# IRIS1-DLB.net
KiCad netlist of a schematic drawn in Altium Designer
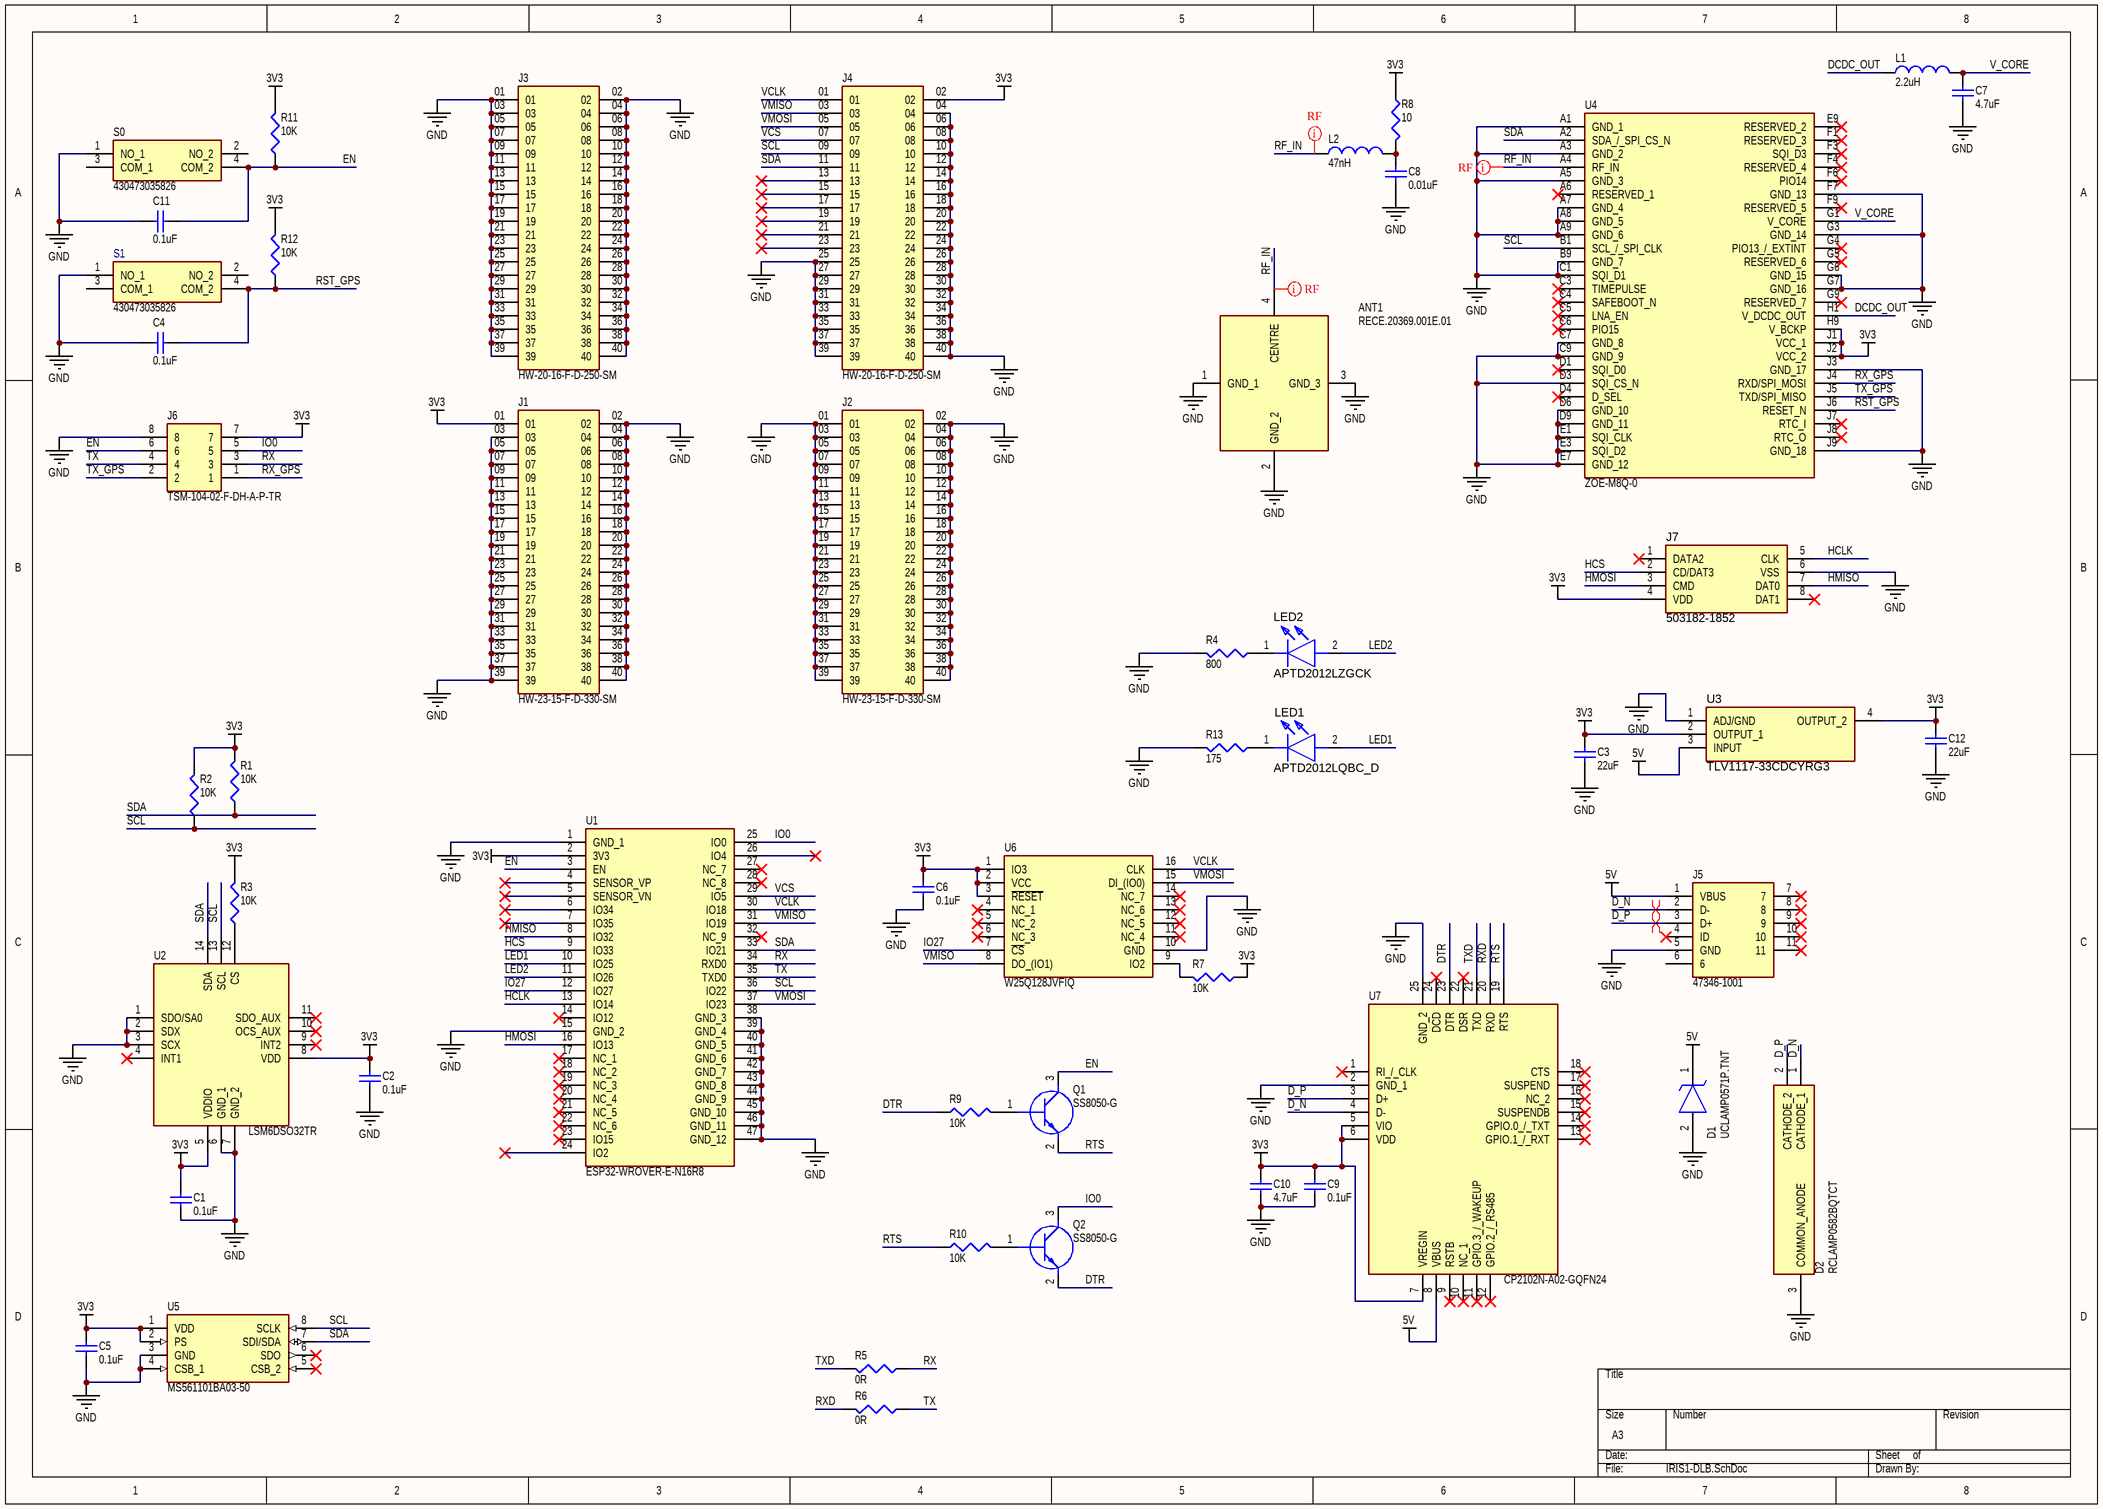
[diagram p0: IRIS1-DLB.SchDoc]

(export (version "E")
  (design (tool "Eeschema 10.0.6"))
  (components
    (comp (ref "ANT1")
      (value "RECE.20369.001E.01")
      (footprint "SamacSys:RECE20369001E01")
      (description "Antenna")
      (fields (field (name "MOUSER PART NUMBER") "960-RECE.20369001E01"))
      (libsource (lib "*") (part "RECE.20369.001E.01"))
    )
    (comp (ref "C1")
      (value "0.1uF")
      (footprint "1608[0603]")
      (description "Capacitor")
      (fields (field (name "PUBLISHER") "Altium Limited"))
      (libsource (lib "Miscellaneous Devices") (part "Cap"))
    )
    (comp (ref "C2")
      (value "0.1uF")
      (footprint "1608[0603]")
      (description "Capacitor")
      (fields (field (name "PUBLISHER") "Altium Limited"))
      (libsource (lib "Miscellaneous Devices") (part "Cap"))
    )
    (comp (ref "C3")
      (value "22uF")
      (footprint "1608[0603]")
      (description "Capacitor")
      (fields (field (name "PUBLISHER") "Altium Limited"))
      (libsource (lib "Miscellaneous Devices") (part "Cap"))
    )
    (comp (ref "C4")
      (value "0.1uF")
      (footprint "1608[0603]")
      (description "Capacitor")
      (fields (field (name "PUBLISHER") "Altium Limited"))
      (libsource (lib "Miscellaneous Devices") (part "Cap"))
    )
    (comp (ref "C5")
      (value "0.1uF")
      (footprint "1608[0603]")
      (description "Capacitor")
      (fields (field (name "PUBLISHER") "Altium Limited"))
      (libsource (lib "Miscellaneous Devices") (part "Cap"))
    )
    (comp (ref "C6")
      (value "0.1uF")
      (footprint "1608[0603]")
      (description "Capacitor")
      (fields (field (name "PUBLISHER") "Altium Limited"))
      (libsource (lib "Miscellaneous Devices") (part "Cap"))
    )
    (comp (ref "C7")
      (value "4.7uF")
      (footprint "1608[0603]")
      (description "Capacitor")
      (fields (field (name "PUBLISHER") "Altium Limited"))
      (libsource (lib "Miscellaneous Devices") (part "Cap"))
    )
    (comp (ref "C8")
      (value "0.01uF")
      (footprint "1608[0603]")
      (description "Capacitor")
      (fields (field (name "PUBLISHER") "Altium Limited"))
      (libsource (lib "Miscellaneous Devices") (part "Cap"))
    )
    (comp (ref "C9")
      (value "0.1uF")
      (footprint "1608[0603]")
      (description "Capacitor")
      (fields (field (name "PUBLISHER") "Altium Limited"))
      (libsource (lib "Miscellaneous Devices") (part "Cap"))
    )
    (comp (ref "C10")
      (value "4.7uF")
      (footprint "1608[0603]")
      (description "Capacitor")
      (fields (field (name "PUBLISHER") "Altium Limited"))
      (libsource (lib "Miscellaneous Devices") (part "Cap"))
    )
    (comp (ref "C11")
      (value "0.1uF")
      (footprint "1608[0603]")
      (description "Capacitor")
      (fields (field (name "PUBLISHER") "Altium Limited"))
      (libsource (lib "Miscellaneous Devices") (part "Cap"))
    )
    (comp (ref "C12")
      (value "22uF")
      (footprint "1608[0603]")
      (description "Capacitor")
      (fields (field (name "PUBLISHER") "Altium Limited"))
      (libsource (lib "Miscellaneous Devices") (part "Cap"))
    )
    (comp (ref "D1")
      (value "UCLAMP0571P.TNT")
      (footprint "SamacSys:DIOC1610X55N")
      (description "TVS Diode (Uni-directional)")
      (fields (field (name "MOUSER PART NUMBER") "947-UCLAMP0571P.TNT"))
      (libsource (lib "*") (part "UCLAMP0571P.TNT"))
    )
    (comp (ref "D2")
      (value "RCLAMP0582BQTCT")
      (footprint "SamacSys:SOT50P160X90-3N")
      (description "TVS Diode (Uni-directional)")
      (fields (field (name "MOUSER PART NUMBER") "947-RCLAMP0582BQTCT"))
      (libsource (lib "*") (part "RCLAMP0582BQTCT"))
    )
    (comp (ref "J1")
      (value "HW-23-15-F-D-330-SM")
      (footprint "SAMTEC_HW-20-16-F-D-250-SM")
      (fields (field (name "MF") "Samtec") (field (name "MP") "HW-20-08-G-D-350-100"))
      (libsource (lib "HW-20-XX-XX-D-XXX-XXX") (part "HW-20-XX-XX-D-XXX-XXX"))
    )
    (comp (ref "J2")
      (value "HW-23-15-F-D-330-SM")
      (footprint "SAMTEC_HW-20-16-F-D-250-SM")
      (fields (field (name "MF") "Samtec") (field (name "MP") "HW-20-08-G-D-350-100"))
      (libsource (lib "HW-20-XX-XX-D-XXX-XXX") (part "HW-20-XX-XX-D-XXX-XXX"))
    )
    (comp (ref "J3")
      (value "HW-20-16-F-D-250-SM")
      (footprint "SAMTEC_HW-20-16-F-D-250-SM")
      (libsource (lib "HW-20-16-F-D-250-SM") (part "HW-20-16-F-D-250-SM"))
    )
    (comp (ref "J4")
      (value "HW-20-16-F-D-250-SM")
      (footprint "SAMTEC_HW-20-16-F-D-250-SM")
      (libsource (lib "HW-20-16-F-D-250-SM") (part "HW-20-16-F-D-250-SM"))
    )
    (comp (ref "J5")
      (value "47346-1001")
      (footprint "SamacSys:473461001")
      (description "Connector")
      (fields (field (name "MOUSER PART NUMBER") "538-47346-1001"))
      (libsource (lib "*") (part "47346-1001"))
    )
    (comp (ref "J6")
      (value "TSM-104-02-F-DH-A-P-TR")
      (footprint "SamacSys:TSM-104-ZZ-YYY-DH-A-P-TR")
      (description "Connector")
      (libsource (lib "*") (part "TSM-104-02-F-DH-A-P-TR"))
    )
    (comp (ref "J7")
      (value "503182-1852")
      (footprint "SamacSys:5031821852")
      (description "Connector")
      (fields (field (name "MOUSER PART NUMBER") "538-503182-1852"))
      (libsource (lib "*") (part "503182-1852"))
    )
    (comp (ref "L1")
      (value "2.2uH")
      (footprint "0402-A")
      (description "Inductor")
      (fields (field (name "PUBLISHER") "Altium Limited"))
      (libsource (lib "Miscellaneous Devices") (part "Inductor"))
    )
    (comp (ref "L2")
      (value "47nH")
      (footprint "0402-A")
      (description "Inductor")
      (fields (field (name "PUBLISHER") "Altium Limited"))
      (libsource (lib "Miscellaneous Devices") (part "Inductor"))
    )
    (comp (ref "LED1")
      (value "APTD2012LQBC_D")
      (footprint "SamacSys:LEDC2012X120N")
      (description "LED")
      (fields
        (field (name "MANUFACTURER_PART_NUMBER") "APTD2012LQBC/D")
        (field (name "MOUSER PART NUMBER") "604-APTD2012LQBCD")
      )
      (libsource (lib "*") (part "APTD2012LQBC_D"))
    )
    (comp (ref "LED2")
      (value "APTD2012LZGCK")
      (footprint "SamacSys:LEDC2012X105N")
      (description "LED")
      (fields (field (name "MOUSER PART NUMBER") "604-APTD2012LZGCK"))
      (libsource (lib "*") (part "APTD2012LZGCK"))
    )
    (comp (ref "Q1")
      (value "SS8050-G")
      (footprint "SamacSys:SOT95P240X115-3N")
      (description "Transistor BJT NPN")
      (fields (field (name "MOUSER PART NUMBER") "750-SS8050-G"))
      (libsource (lib "*") (part "SS8050-G"))
    )
    (comp (ref "Q2")
      (value "SS8050-G")
      (footprint "SamacSys:SOT95P240X115-3N")
      (description "Transistor BJT NPN")
      (fields (field (name "MOUSER PART NUMBER") "750-SS8050-G"))
      (libsource (lib "*") (part "SS8050-G"))
    )
    (comp (ref "R1")
      (value "10K")
      (footprint "J1-0603")
      (description "Resistor")
      (fields (field (name "PUBLISHER") "Altium Limited"))
      (libsource (lib "Miscellaneous Devices") (part "Res3"))
    )
    (comp (ref "R2")
      (value "10K")
      (footprint "J1-0603")
      (description "Resistor")
      (fields (field (name "PUBLISHER") "Altium Limited"))
      (libsource (lib "Miscellaneous Devices") (part "Res3"))
    )
    (comp (ref "R3")
      (value "10K")
      (footprint "J1-0603")
      (description "Resistor")
      (fields (field (name "PUBLISHER") "Altium Limited"))
      (libsource (lib "Miscellaneous Devices") (part "Res3"))
    )
    (comp (ref "R4")
      (value "800")
      (footprint "J1-0603")
      (description "Resistor")
      (fields (field (name "PUBLISHER") "Altium Limited"))
      (libsource (lib "Miscellaneous Devices") (part "Res3"))
    )
    (comp (ref "R5")
      (value "0R")
      (footprint "J1-0603")
      (description "Resistor")
      (fields (field (name "PUBLISHER") "Altium Limited"))
      (libsource (lib "Miscellaneous Devices") (part "Res3"))
    )
    (comp (ref "R6")
      (value "0R")
      (footprint "J1-0603")
      (description "Resistor")
      (fields (field (name "PUBLISHER") "Altium Limited"))
      (libsource (lib "Miscellaneous Devices") (part "Res3"))
    )
    (comp (ref "R7")
      (value "10K")
      (footprint "J1-0603")
      (description "Resistor")
      (fields (field (name "PUBLISHER") "Altium Limited"))
      (libsource (lib "Miscellaneous Devices") (part "Res3"))
    )
    (comp (ref "R8")
      (value "10")
      (footprint "J1-0603")
      (description "Resistor")
      (fields (field (name "PUBLISHER") "Altium Limited"))
      (libsource (lib "Miscellaneous Devices") (part "Res3"))
    )
    (comp (ref "R9")
      (value "10K")
      (footprint "J1-0603")
      (description "Resistor")
      (fields (field (name "PUBLISHER") "Altium Limited"))
      (libsource (lib "Miscellaneous Devices") (part "Res3"))
    )
    (comp (ref "R10")
      (value "10K")
      (footprint "J1-0603")
      (description "Resistor")
      (fields (field (name "PUBLISHER") "Altium Limited"))
      (libsource (lib "Miscellaneous Devices") (part "Res3"))
    )
    (comp (ref "R11")
      (value "10K")
      (footprint "J1-0603")
      (description "Resistor")
      (fields (field (name "PUBLISHER") "Altium Limited"))
      (libsource (lib "Miscellaneous Devices") (part "Res3"))
    )
    (comp (ref "R12")
      (value "10K")
      (footprint "J1-0603")
      (description "Resistor")
      (fields (field (name "PUBLISHER") "Altium Limited"))
      (libsource (lib "Miscellaneous Devices") (part "Res3"))
    )
    (comp (ref "R13")
      (value "175")
      (footprint "J1-0603")
      (description "Resistor")
      (fields (field (name "PUBLISHER") "Altium Limited"))
      (libsource (lib "Miscellaneous Devices") (part "Res3"))
    )
    (comp (ref "S0")
      (value "430473035826")
      (footprint "SamacSys:430473035826")
      (description "Switch")
      (fields (field (name "MOUSER PART NUMBER") "710-430473035826"))
      (libsource (lib "*") (part "430473035826"))
    )
    (comp (ref "S1")
      (value "430473035826")
      (footprint "SamacSys:430473035826")
      (description "Switch")
      (fields (field (name "MOUSER PART NUMBER") "710-430473035826"))
      (libsource (lib "*") (part "430473035826"))
    )
    (comp (ref "U1")
      (value "ESP32-WROVER-E-N16R8")
      (footprint "SamacSys:ESP32WROVEREN16R8")
      (description "Integrated Circuit")
      (fields (field (name "MOUSER PART NUMBER") "356-ESP32WRVE22864PC"))
      (libsource (lib "*") (part "ESP32-WROVER-E-N16R8"))
    )
    (comp (ref "U2")
      (value "LSM6DSO32TR")
      (footprint "SamacSys:LGA-14(2.5X3X0.86)")
      (description "Accelerometer")
      (fields
        (field (name "MANUFACTURER_PART_NUMBER") "LSM6DSOTR")
        (field (name "MOUSER PART NUMBER") "511-LSM6DSOTR")
      )
      (libsource (lib "*") (part "LSM6DSOTR"))
    )
    (comp (ref "U3")
      (value "TLV1117-33CDCYRG3")
      (footprint "SamacSys:SOT230P700X180-4N")
      (description "Integrated Circuit")
      (fields (field (name "MOUSER PART NUMBER") "595-TLV111733CDCYRG3"))
      (libsource (lib "*") (part "TLV1117-33CDCYRG3"))
    )
    (comp (ref "U4")
      (value "ZOE-M8Q-0")
      (footprint "SamacSys:ZOEM8Q0")
      (description "Integrated Circuit")
      (fields (field (name "MOUSER PART NUMBER") "377-ZOE-M8Q-0"))
      (libsource (lib "*") (part "ZOE-M8Q-0"))
    )
    (comp (ref "U5")
      (value "MS561101BA03-50")
      (footprint "SamacSys:MS561101BA03-50")
      (description "Integrated Circuit")
      (fields (field (name "MOUSER PART NUMBER") "824-MS561101BA03-50"))
      (libsource (lib "*") (part "MS561101BA03-50"))
    )
    (comp (ref "U6")
      (value "W25Q128JVFIQ")
      (footprint "SamacSys:SOIC127P1032X264-16N")
      (description "Integrated Circuit")
      (fields (field (name "MOUSER PART NUMBER") "454-W25Q128JVFIQ"))
      (libsource (lib "*") (part "W25Q128JVFIQ"))
    )
    (comp (ref "U7")
      (value "CP2102N-A02-GQFN24")
      (footprint "SamacSys:QFN50P400X400X80-25N-D")
      (description "Integrated Circuit")
      (fields (field (name "MOUSER PART NUMBER") "634-CP2102NA02GQFN24"))
      (libsource (lib "*") (part "CP2102N-A02-GQFN24"))
    )
  )
  (nets
    (net (code "1") (name "/DCDC_OUT") (class "Default")
      (node (ref "L1") (pin "1") (pinfunction "1_1") (pintype "passive"))
      (node (ref "U4") (pin "H1") (pinfunction "V_DCDC_OUT_H1") (pintype "passive"))
    )
    (net (code "2") (name "/DTR") (class "Default")
      (node (ref "Q2") (pin "2") (pinfunction "E_2") (pintype "passive"))
      (node (ref "R9") (pin "1") (pinfunction "1_1") (pintype "passive"))
      (node (ref "U7") (pin "23") (pinfunction "DTR_23") (pintype "passive"))
    )
    (net (code "3") (name "/D_N") (class "Default")
      (node (ref "D2") (pin "1") (pinfunction "CATHODE_1_1") (pintype "passive"))
      (node (ref "J5") (pin "2") (pinfunction "D-_2") (pintype "passive"))
      (node (ref "U7") (pin "4") (pinfunction "D-_4") (pintype "passive"))
    )
    (net (code "4") (name "/D_P") (class "Default")
      (node (ref "D2") (pin "2") (pinfunction "CATHODE_2_2") (pintype "passive"))
      (node (ref "J5") (pin "3") (pinfunction "D+_3") (pintype "passive"))
      (node (ref "U7") (pin "3") (pinfunction "D+_3") (pintype "passive"))
    )
    (net (code "5") (name "/EN") (class "Default")
      (node (ref "C11") (pin "2") (pinfunction "2_2") (pintype "passive"))
      (node (ref "J6") (pin "6") (pinfunction "6_6") (pintype "passive"))
      (node (ref "Q1") (pin "3") (pinfunction "C_3") (pintype "passive"))
      (node (ref "R11") (pin "1") (pinfunction "1_1") (pintype "passive"))
      (node (ref "S0") (pin "4") (pinfunction "COM_2_4") (pintype "passive"))
      (node (ref "U1") (pin "3") (pinfunction "EN_3") (pintype "passive"))
    )
    (net (code "6") (name "/HCLK") (class "Default")
      (node (ref "J7") (pin "5") (pinfunction "CLK_5") (pintype "passive"))
      (node (ref "U1") (pin "13") (pinfunction "IO14_13") (pintype "passive"))
    )
    (net (code "7") (name "/HCS") (class "Default")
      (node (ref "J7") (pin "2") (pinfunction "CD/DAT3_2") (pintype "passive"))
      (node (ref "U1") (pin "9") (pinfunction "IO33_9") (pintype "passive"))
    )
    (net (code "8") (name "/HMISO") (class "Default")
      (node (ref "J7") (pin "7") (pinfunction "DAT0_7") (pintype "passive"))
      (node (ref "U1") (pin "8") (pinfunction "IO32_8") (pintype "passive"))
    )
    (net (code "9") (name "/HMOSI") (class "Default")
      (node (ref "J7") (pin "3") (pinfunction "CMD_3") (pintype "passive"))
      (node (ref "U1") (pin "16") (pinfunction "IO13_16") (pintype "passive"))
    )
    (net (code "10") (name "/IO0") (class "Default")
      (node (ref "J6") (pin "5") (pinfunction "5_5") (pintype "passive"))
      (node (ref "Q2") (pin "3") (pinfunction "C_3") (pintype "passive"))
      (node (ref "U1") (pin "25") (pinfunction "IO0_25") (pintype "passive"))
    )
    (net (code "11") (name "/IO27") (class "Default")
      (node (ref "U1") (pin "12") (pinfunction "IO27_12") (pintype "passive"))
      (node (ref "U6") (pin "7") (pinfunction "~{CS}_7") (pintype "passive"))
    )
    (net (code "12") (name "/LED1") (class "Default")
      (node (ref "LED1") (pin "2") (pinfunction "A_2") (pintype "passive"))
      (node (ref "U1") (pin "10") (pinfunction "IO25_10") (pintype "passive"))
    )
    (net (code "13") (name "/LED2") (class "Default")
      (node (ref "LED2") (pin "2") (pinfunction "A_2") (pintype "passive"))
      (node (ref "U1") (pin "11") (pinfunction "IO26_11") (pintype "passive"))
    )
    (net (code "14") (name "/RF_IN") (class "Default")
      (node (ref "ANT1") (pin "4") (pinfunction "CENTRE_4") (pintype "passive"))
      (node (ref "L2") (pin "1") (pinfunction "1_1") (pintype "passive"))
      (node (ref "U4") (pin "A4") (pinfunction "RF_IN_A4") (pintype "passive"))
    )
    (net (code "15") (name "/RST_GPS") (class "Default")
      (node (ref "C4") (pin "2") (pinfunction "2_2") (pintype "passive"))
      (node (ref "R12") (pin "1") (pinfunction "1_1") (pintype "passive"))
      (node (ref "S1") (pin "4") (pinfunction "COM_2_4") (pintype "passive"))
      (node (ref "U4") (pin "J6") (pinfunction "RESET_N_J6") (pintype "passive"))
    )
    (net (code "16") (name "/RTS") (class "Default")
      (node (ref "Q1") (pin "2") (pinfunction "E_2") (pintype "passive"))
      (node (ref "R10") (pin "1") (pinfunction "1_1") (pintype "passive"))
      (node (ref "U7") (pin "19") (pinfunction "RTS_19") (pintype "passive"))
    )
    (net (code "17") (name "/RX") (class "Default")
      (node (ref "J6") (pin "3") (pinfunction "3_3") (pintype "passive"))
      (node (ref "R5") (pin "1") (pinfunction "1_1") (pintype "passive"))
      (node (ref "U1") (pin "34") (pinfunction "RXD0_34") (pintype "passive"))
    )
    (net (code "18") (name "/RXD") (class "Default")
      (node (ref "R6") (pin "2") (pinfunction "2_2") (pintype "passive"))
      (node (ref "U7") (pin "20") (pinfunction "RXD_20") (pintype "passive"))
    )
    (net (code "19") (name "/RX_GPS") (class "Default")
      (node (ref "J6") (pin "1") (pinfunction "1_1") (pintype "passive"))
      (node (ref "U4") (pin "J4") (pinfunction "RXD/SPI_MOSI_J4") (pintype "passive"))
    )
    (net (code "20") (name "/SCL") (class "Default")
      (node (ref "J4") (pin "09") (pinfunction "09_09") (pintype "passive"))
      (node (ref "R2") (pin "1") (pinfunction "1_1") (pintype "passive"))
      (node (ref "U1") (pin "36") (pinfunction "IO22_36") (pintype "passive"))
      (node (ref "U2") (pin "13") (pinfunction "SCL_13") (pintype "passive"))
      (node (ref "U4") (pin "B1") (pinfunction "SCL_/_SPI_CLK_B1") (pintype "passive"))
      (node (ref "U5") (pin "8") (pinfunction "SCLK_8") (pintype "input"))
    )
    (net (code "21") (name "/SDA") (class "Default")
      (node (ref "J4") (pin "11") (pinfunction "11_11") (pintype "passive"))
      (node (ref "R1") (pin "1") (pinfunction "1_1") (pintype "passive"))
      (node (ref "U1") (pin "33") (pinfunction "IO21_33") (pintype "passive"))
      (node (ref "U2") (pin "14") (pinfunction "SDA_14") (pintype "passive"))
      (node (ref "U4") (pin "A2") (pinfunction "SDA_/_SPI_CS_N_A2") (pintype "passive"))
      (node (ref "U5") (pin "7") (pinfunction "SDI/SDA_7") (pintype "bidirectional"))
    )
    (net (code "22") (name "/TX") (class "Default")
      (node (ref "J6") (pin "4") (pinfunction "4_4") (pintype "passive"))
      (node (ref "R6") (pin "1") (pinfunction "1_1") (pintype "passive"))
      (node (ref "U1") (pin "35") (pinfunction "TXD0_35") (pintype "passive"))
    )
    (net (code "23") (name "/TXD") (class "Default")
      (node (ref "R5") (pin "2") (pinfunction "2_2") (pintype "passive"))
      (node (ref "U7") (pin "21") (pinfunction "TXD_21") (pintype "passive"))
    )
    (net (code "24") (name "/TX_GPS") (class "Default")
      (node (ref "J6") (pin "2") (pinfunction "2_2") (pintype "passive"))
      (node (ref "U4") (pin "J5") (pinfunction "TXD/SPI_MISO_J5") (pintype "passive"))
    )
    (net (code "25") (name "/VCLK") (class "Default")
      (node (ref "J4") (pin "01") (pinfunction "01_01") (pintype "passive"))
      (node (ref "U1") (pin "30") (pinfunction "IO18_30") (pintype "passive"))
      (node (ref "U6") (pin "16") (pinfunction "CLK_16") (pintype "passive"))
    )
    (net (code "26") (name "/VCS") (class "Default")
      (node (ref "J4") (pin "07") (pinfunction "07_07") (pintype "passive"))
      (node (ref "U1") (pin "29") (pinfunction "IO5_29") (pintype "passive"))
    )
    (net (code "27") (name "/VMISO") (class "Default")
      (node (ref "J4") (pin "03") (pinfunction "03_03") (pintype "passive"))
      (node (ref "U1") (pin "31") (pinfunction "IO19_31") (pintype "passive"))
      (node (ref "U6") (pin "8") (pinfunction "DO_(IO1)_8") (pintype "passive"))
    )
    (net (code "28") (name "/VMOSI") (class "Default")
      (node (ref "J4") (pin "05") (pinfunction "05_05") (pintype "passive"))
      (node (ref "U1") (pin "37") (pinfunction "IO23_37") (pintype "passive"))
      (node (ref "U6") (pin "15") (pinfunction "DI_(IO0)_15") (pintype "passive"))
    )
    (net (code "29") (name "/V_CORE") (class "Default")
      (node (ref "C7") (pin "2") (pinfunction "2_2") (pintype "passive"))
      (node (ref "L1") (pin "2") (pinfunction "2_2") (pintype "passive"))
      (node (ref "U4") (pin "G1") (pinfunction "V_CORE_G1") (pintype "passive"))
    )
    (net (code "30") (name "3V3") (class "Default")
      (node (ref "C1") (pin "2") (pinfunction "2_2") (pintype "passive"))
      (node (ref "C10") (pin "2") (pinfunction "2_2") (pintype "passive"))
      (node (ref "C12") (pin "2") (pinfunction "2_2") (pintype "passive"))
      (node (ref "C2") (pin "2") (pinfunction "2_2") (pintype "passive"))
      (node (ref "C3") (pin "2") (pinfunction "2_2") (pintype "passive"))
      (node (ref "C5") (pin "2") (pinfunction "2_2") (pintype "passive"))
      (node (ref "C6") (pin "2") (pinfunction "2_2") (pintype "passive"))
      (node (ref "C9") (pin "2") (pinfunction "2_2") (pintype "passive"))
      (node (ref "J1") (pin "01") (pinfunction "01_01") (pintype "passive"))
      (node (ref "J4") (pin "02") (pinfunction "02_02") (pintype "passive"))
      (node (ref "J6") (pin "7") (pinfunction "7_7") (pintype "passive"))
      (node (ref "J7") (pin "4") (pinfunction "VDD_4") (pintype "passive"))
      (node (ref "R1") (pin "2") (pinfunction "2_2") (pintype "passive"))
      (node (ref "R11") (pin "2") (pinfunction "2_2") (pintype "passive"))
      (node (ref "R12") (pin "2") (pinfunction "2_2") (pintype "passive"))
      (node (ref "R2") (pin "2") (pinfunction "2_2") (pintype "passive"))
      (node (ref "R3") (pin "2") (pinfunction "2_2") (pintype "passive"))
      (node (ref "R7") (pin "1") (pinfunction "1_1") (pintype "passive"))
      (node (ref "R8") (pin "1") (pinfunction "1_1") (pintype "passive"))
      (node (ref "U1") (pin "2") (pinfunction "3V3_2") (pintype "passive"))
      (node (ref "U2") (pin "5") (pinfunction "VDDIO_5") (pintype "passive"))
      (node (ref "U2") (pin "8") (pinfunction "VDD_8") (pintype "passive"))
      (node (ref "U3") (pin "2") (pinfunction "OUTPUT_1_2") (pintype "passive"))
      (node (ref "U3") (pin "4") (pinfunction "OUTPUT_2_4") (pintype "passive"))
      (node (ref "U4") (pin "H9") (pinfunction "V_BCKP_H9") (pintype "passive"))
      (node (ref "U4") (pin "J1") (pinfunction "VCC_1_J1") (pintype "passive"))
      (node (ref "U4") (pin "J2") (pinfunction "VCC_2_J2") (pintype "passive"))
      (node (ref "U5") (pin "1") (pinfunction "VDD_1") (pintype "power_in"))
      (node (ref "U5") (pin "2") (pinfunction "PS_2") (pintype "input"))
      (node (ref "U6") (pin "1") (pinfunction "IO3_1") (pintype "passive"))
      (node (ref "U6") (pin "2") (pinfunction "VCC_2") (pintype "passive"))
      (node (ref "U6") (pin "3") (pinfunction "~{RESET}_3") (pintype "passive"))
      (node (ref "U7") (pin "5") (pinfunction "VIO_5") (pintype "passive"))
      (node (ref "U7") (pin "6") (pinfunction "VDD_6") (pintype "passive"))
      (node (ref "U7") (pin "7") (pinfunction "VREGIN_7") (pintype "passive"))
    )
    (net (code "31") (name "5V") (class "Default")
      (node (ref "D1") (pin "1") (pinfunction "K_1") (pintype "passive"))
      (node (ref "J5") (pin "1") (pinfunction "VBUS_1") (pintype "passive"))
      (node (ref "U3") (pin "3") (pinfunction "INPUT_3") (pintype "passive"))
      (node (ref "U7") (pin "8") (pinfunction "VBUS_8") (pintype "passive"))
    )
    (net (code "32") (name "GND") (class "Default")
      (node (ref "ANT1") (pin "1") (pinfunction "GND_1_1") (pintype "passive"))
      (node (ref "ANT1") (pin "2") (pinfunction "GND_2_2") (pintype "passive"))
      (node (ref "ANT1") (pin "3") (pinfunction "GND_3_3") (pintype "passive"))
      (node (ref "C1") (pin "1") (pinfunction "1_1") (pintype "passive"))
      (node (ref "C10") (pin "1") (pinfunction "1_1") (pintype "passive"))
      (node (ref "C11") (pin "1") (pinfunction "1_1") (pintype "passive"))
      (node (ref "C12") (pin "1") (pinfunction "1_1") (pintype "passive"))
      (node (ref "C2") (pin "1") (pinfunction "1_1") (pintype "passive"))
      (node (ref "C3") (pin "1") (pinfunction "1_1") (pintype "passive"))
      (node (ref "C4") (pin "1") (pinfunction "1_1") (pintype "passive"))
      (node (ref "C5") (pin "1") (pinfunction "1_1") (pintype "passive"))
      (node (ref "C6") (pin "1") (pinfunction "1_1") (pintype "passive"))
      (node (ref "C7") (pin "1") (pinfunction "1_1") (pintype "passive"))
      (node (ref "C8") (pin "1") (pinfunction "1_1") (pintype "passive"))
      (node (ref "C9") (pin "1") (pinfunction "1_1") (pintype "passive"))
      (node (ref "D1") (pin "2") (pinfunction "A_2") (pintype "passive"))
      (node (ref "D2") (pin "3") (pinfunction "COMMON_ANODE_3") (pintype "passive"))
      (node (ref "J1") (pin "02") (pinfunction "02_02") (pintype "passive"))
      (node (ref "J1") (pin "03") (pinfunction "03_03") (pintype "passive"))
      (node (ref "J1") (pin "04") (pinfunction "04_04") (pintype "passive"))
      (node (ref "J1") (pin "05") (pinfunction "05_05") (pintype "passive"))
      (node (ref "J1") (pin "06") (pinfunction "06_06") (pintype "passive"))
      (node (ref "J1") (pin "07") (pinfunction "07_07") (pintype "passive"))
      (node (ref "J1") (pin "08") (pinfunction "08_08") (pintype "passive"))
      (node (ref "J1") (pin "09") (pinfunction "09_09") (pintype "passive"))
      (node (ref "J1") (pin "10") (pinfunction "10_10") (pintype "passive"))
      (node (ref "J1") (pin "11") (pinfunction "11_11") (pintype "passive"))
      (node (ref "J1") (pin "12") (pinfunction "12_12") (pintype "passive"))
      (node (ref "J1") (pin "13") (pinfunction "13_13") (pintype "passive"))
      (node (ref "J1") (pin "14") (pinfunction "14_14") (pintype "passive"))
      (node (ref "J1") (pin "15") (pinfunction "15_15") (pintype "passive"))
      (node (ref "J1") (pin "16") (pinfunction "16_16") (pintype "passive"))
      (node (ref "J1") (pin "17") (pinfunction "17_17") (pintype "passive"))
      (node (ref "J1") (pin "18") (pinfunction "18_18") (pintype "passive"))
      (node (ref "J1") (pin "19") (pinfunction "19_19") (pintype "passive"))
      (node (ref "J1") (pin "20") (pinfunction "20_20") (pintype "passive"))
      (node (ref "J1") (pin "21") (pinfunction "21_21") (pintype "passive"))
      (node (ref "J1") (pin "22") (pinfunction "22_22") (pintype "passive"))
      (node (ref "J1") (pin "23") (pinfunction "23_23") (pintype "passive"))
      (node (ref "J1") (pin "24") (pinfunction "24_24") (pintype "passive"))
      (node (ref "J1") (pin "25") (pinfunction "25_25") (pintype "passive"))
      (node (ref "J1") (pin "26") (pinfunction "26_26") (pintype "passive"))
      (node (ref "J1") (pin "27") (pinfunction "27_27") (pintype "passive"))
      (node (ref "J1") (pin "28") (pinfunction "28_28") (pintype "passive"))
      (node (ref "J1") (pin "29") (pinfunction "29_29") (pintype "passive"))
      (node (ref "J1") (pin "30") (pinfunction "30_30") (pintype "passive"))
      (node (ref "J1") (pin "31") (pinfunction "31_31") (pintype "passive"))
      (node (ref "J1") (pin "32") (pinfunction "32_32") (pintype "passive"))
      (node (ref "J1") (pin "33") (pinfunction "33_33") (pintype "passive"))
      (node (ref "J1") (pin "34") (pinfunction "34_34") (pintype "passive"))
      (node (ref "J1") (pin "35") (pinfunction "35_35") (pintype "passive"))
      (node (ref "J1") (pin "36") (pinfunction "36_36") (pintype "passive"))
      (node (ref "J1") (pin "37") (pinfunction "37_37") (pintype "passive"))
      (node (ref "J1") (pin "38") (pinfunction "38_38") (pintype "passive"))
      (node (ref "J1") (pin "39") (pinfunction "39_39") (pintype "passive"))
      (node (ref "J1") (pin "40") (pinfunction "40_40") (pintype "passive"))
      (node (ref "J2") (pin "01") (pinfunction "01_01") (pintype "passive"))
      (node (ref "J2") (pin "02") (pinfunction "02_02") (pintype "passive"))
      (node (ref "J2") (pin "03") (pinfunction "03_03") (pintype "passive"))
      (node (ref "J2") (pin "04") (pinfunction "04_04") (pintype "passive"))
      (node (ref "J2") (pin "05") (pinfunction "05_05") (pintype "passive"))
      (node (ref "J2") (pin "06") (pinfunction "06_06") (pintype "passive"))
      (node (ref "J2") (pin "07") (pinfunction "07_07") (pintype "passive"))
      (node (ref "J2") (pin "08") (pinfunction "08_08") (pintype "passive"))
      (node (ref "J2") (pin "09") (pinfunction "09_09") (pintype "passive"))
      (node (ref "J2") (pin "10") (pinfunction "10_10") (pintype "passive"))
      (node (ref "J2") (pin "11") (pinfunction "11_11") (pintype "passive"))
      (node (ref "J2") (pin "12") (pinfunction "12_12") (pintype "passive"))
      (node (ref "J2") (pin "13") (pinfunction "13_13") (pintype "passive"))
      (node (ref "J2") (pin "14") (pinfunction "14_14") (pintype "passive"))
      (node (ref "J2") (pin "15") (pinfunction "15_15") (pintype "passive"))
      (node (ref "J2") (pin "16") (pinfunction "16_16") (pintype "passive"))
      (node (ref "J2") (pin "17") (pinfunction "17_17") (pintype "passive"))
      (node (ref "J2") (pin "18") (pinfunction "18_18") (pintype "passive"))
      (node (ref "J2") (pin "19") (pinfunction "19_19") (pintype "passive"))
      (node (ref "J2") (pin "20") (pinfunction "20_20") (pintype "passive"))
      (node (ref "J2") (pin "21") (pinfunction "21_21") (pintype "passive"))
      (node (ref "J2") (pin "22") (pinfunction "22_22") (pintype "passive"))
      (node (ref "J2") (pin "23") (pinfunction "23_23") (pintype "passive"))
      (node (ref "J2") (pin "24") (pinfunction "24_24") (pintype "passive"))
      (node (ref "J2") (pin "25") (pinfunction "25_25") (pintype "passive"))
      (node (ref "J2") (pin "26") (pinfunction "26_26") (pintype "passive"))
      (node (ref "J2") (pin "27") (pinfunction "27_27") (pintype "passive"))
      (node (ref "J2") (pin "28") (pinfunction "28_28") (pintype "passive"))
      (node (ref "J2") (pin "29") (pinfunction "29_29") (pintype "passive"))
      (node (ref "J2") (pin "30") (pinfunction "30_30") (pintype "passive"))
      (node (ref "J2") (pin "31") (pinfunction "31_31") (pintype "passive"))
      (node (ref "J2") (pin "32") (pinfunction "32_32") (pintype "passive"))
      (node (ref "J2") (pin "33") (pinfunction "33_33") (pintype "passive"))
      (node (ref "J2") (pin "34") (pinfunction "34_34") (pintype "passive"))
      (node (ref "J2") (pin "35") (pinfunction "35_35") (pintype "passive"))
      (node (ref "J2") (pin "36") (pinfunction "36_36") (pintype "passive"))
      (node (ref "J2") (pin "37") (pinfunction "37_37") (pintype "passive"))
      (node (ref "J2") (pin "38") (pinfunction "38_38") (pintype "passive"))
      (node (ref "J2") (pin "39") (pinfunction "39_39") (pintype "passive"))
      (node (ref "J2") (pin "40") (pinfunction "40_40") (pintype "passive"))
      (node (ref "J3") (pin "01") (pinfunction "01_01") (pintype "passive"))
      (node (ref "J3") (pin "02") (pinfunction "02_02") (pintype "passive"))
      (node (ref "J3") (pin "03") (pinfunction "03_03") (pintype "passive"))
      (node (ref "J3") (pin "04") (pinfunction "04_04") (pintype "passive"))
      (node (ref "J3") (pin "05") (pinfunction "05_05") (pintype "passive"))
      (node (ref "J3") (pin "06") (pinfunction "06_06") (pintype "passive"))
      (node (ref "J3") (pin "07") (pinfunction "07_07") (pintype "passive"))
      (node (ref "J3") (pin "08") (pinfunction "08_08") (pintype "passive"))
      (node (ref "J3") (pin "09") (pinfunction "09_09") (pintype "passive"))
      (node (ref "J3") (pin "10") (pinfunction "10_10") (pintype "passive"))
      (node (ref "J3") (pin "11") (pinfunction "11_11") (pintype "passive"))
      (node (ref "J3") (pin "12") (pinfunction "12_12") (pintype "passive"))
      (node (ref "J3") (pin "13") (pinfunction "13_13") (pintype "passive"))
      (node (ref "J3") (pin "14") (pinfunction "14_14") (pintype "passive"))
      (node (ref "J3") (pin "15") (pinfunction "15_15") (pintype "passive"))
      (node (ref "J3") (pin "16") (pinfunction "16_16") (pintype "passive"))
      (node (ref "J3") (pin "17") (pinfunction "17_17") (pintype "passive"))
      (node (ref "J3") (pin "18") (pinfunction "18_18") (pintype "passive"))
      (node (ref "J3") (pin "19") (pinfunction "19_19") (pintype "passive"))
      (node (ref "J3") (pin "20") (pinfunction "20_20") (pintype "passive"))
      (node (ref "J3") (pin "21") (pinfunction "21_21") (pintype "passive"))
      (node (ref "J3") (pin "22") (pinfunction "22_22") (pintype "passive"))
      (node (ref "J3") (pin "23") (pinfunction "23_23") (pintype "passive"))
      (node (ref "J3") (pin "24") (pinfunction "24_24") (pintype "passive"))
      (node (ref "J3") (pin "25") (pinfunction "25_25") (pintype "passive"))
      (node (ref "J3") (pin "26") (pinfunction "26_26") (pintype "passive"))
      (node (ref "J3") (pin "27") (pinfunction "27_27") (pintype "passive"))
      (node (ref "J3") (pin "28") (pinfunction "28_28") (pintype "passive"))
      (node (ref "J3") (pin "29") (pinfunction "29_29") (pintype "passive"))
      (node (ref "J3") (pin "30") (pinfunction "30_30") (pintype "passive"))
      (node (ref "J3") (pin "31") (pinfunction "31_31") (pintype "passive"))
      (node (ref "J3") (pin "32") (pinfunction "32_32") (pintype "passive"))
      (node (ref "J3") (pin "33") (pinfunction "33_33") (pintype "passive"))
      (node (ref "J3") (pin "34") (pinfunction "34_34") (pintype "passive"))
      (node (ref "J3") (pin "35") (pinfunction "35_35") (pintype "passive"))
      (node (ref "J3") (pin "36") (pinfunction "36_36") (pintype "passive"))
      (node (ref "J3") (pin "37") (pinfunction "37_37") (pintype "passive"))
      (node (ref "J3") (pin "38") (pinfunction "38_38") (pintype "passive"))
      (node (ref "J3") (pin "39") (pinfunction "39_39") (pintype "passive"))
      (node (ref "J3") (pin "40") (pinfunction "40_40") (pintype "passive"))
      (node (ref "J4") (pin "04") (pinfunction "04_04") (pintype "passive"))
      (node (ref "J4") (pin "06") (pinfunction "06_06") (pintype "passive"))
      (node (ref "J4") (pin "08") (pinfunction "08_08") (pintype "passive"))
      (node (ref "J4") (pin "10") (pinfunction "10_10") (pintype "passive"))
      (node (ref "J4") (pin "12") (pinfunction "12_12") (pintype "passive"))
      (node (ref "J4") (pin "14") (pinfunction "14_14") (pintype "passive"))
      (node (ref "J4") (pin "16") (pinfunction "16_16") (pintype "passive"))
      (node (ref "J4") (pin "18") (pinfunction "18_18") (pintype "passive"))
      (node (ref "J4") (pin "20") (pinfunction "20_20") (pintype "passive"))
      (node (ref "J4") (pin "22") (pinfunction "22_22") (pintype "passive"))
      (node (ref "J4") (pin "24") (pinfunction "24_24") (pintype "passive"))
      (node (ref "J4") (pin "25") (pinfunction "25_25") (pintype "passive"))
      (node (ref "J4") (pin "26") (pinfunction "26_26") (pintype "passive"))
      (node (ref "J4") (pin "27") (pinfunction "27_27") (pintype "passive"))
      (node (ref "J4") (pin "28") (pinfunction "28_28") (pintype "passive"))
      (node (ref "J4") (pin "29") (pinfunction "29_29") (pintype "passive"))
      (node (ref "J4") (pin "30") (pinfunction "30_30") (pintype "passive"))
      (node (ref "J4") (pin "31") (pinfunction "31_31") (pintype "passive"))
      (node (ref "J4") (pin "32") (pinfunction "32_32") (pintype "passive"))
      (node (ref "J4") (pin "33") (pinfunction "33_33") (pintype "passive"))
      (node (ref "J4") (pin "34") (pinfunction "34_34") (pintype "passive"))
      (node (ref "J4") (pin "35") (pinfunction "35_35") (pintype "passive"))
      (node (ref "J4") (pin "36") (pinfunction "36_36") (pintype "passive"))
      (node (ref "J4") (pin "37") (pinfunction "37_37") (pintype "passive"))
      (node (ref "J4") (pin "38") (pinfunction "38_38") (pintype "passive"))
      (node (ref "J4") (pin "39") (pinfunction "39_39") (pintype "passive"))
      (node (ref "J4") (pin "40") (pinfunction "40_40") (pintype "passive"))
      (node (ref "J5") (pin "5") (pinfunction "GND_5") (pintype "passive"))
      (node (ref "J6") (pin "8") (pinfunction "8_8") (pintype "passive"))
      (node (ref "J7") (pin "6") (pinfunction "VSS_6") (pintype "passive"))
      (node (ref "R13") (pin "2") (pinfunction "2_2") (pintype "passive"))
      (node (ref "R4") (pin "2") (pinfunction "2_2") (pintype "passive"))
      (node (ref "S0") (pin "1") (pinfunction "NO_1_1") (pintype "passive"))
      (node (ref "S1") (pin "1") (pinfunction "NO_1_1") (pintype "passive"))
      (node (ref "U1") (pin "1") (pinfunction "GND_1_1") (pintype "passive"))
      (node (ref "U1") (pin "15") (pinfunction "GND_2_15") (pintype "passive"))
      (node (ref "U1") (pin "38") (pinfunction "GND_3_38") (pintype "passive"))
      (node (ref "U1") (pin "39") (pinfunction "GND_4_39") (pintype "passive"))
      (node (ref "U1") (pin "40") (pinfunction "GND_5_40") (pintype "passive"))
      (node (ref "U1") (pin "41") (pinfunction "GND_6_41") (pintype "passive"))
      (node (ref "U1") (pin "42") (pinfunction "GND_7_42") (pintype "passive"))
      (node (ref "U1") (pin "43") (pinfunction "GND_8_43") (pintype "passive"))
      (node (ref "U1") (pin "44") (pinfunction "GND_9_44") (pintype "passive"))
      (node (ref "U1") (pin "45") (pinfunction "GND_10_45") (pintype "passive"))
      (node (ref "U1") (pin "46") (pinfunction "GND_11_46") (pintype "passive"))
      (node (ref "U1") (pin "47") (pinfunction "GND_12_47") (pintype "passive"))
      (node (ref "U2") (pin "1") (pinfunction "SDO/SA0_1") (pintype "passive"))
      (node (ref "U2") (pin "2") (pinfunction "SDX_2") (pintype "passive"))
      (node (ref "U2") (pin "3") (pinfunction "SCX_3") (pintype "passive"))
      (node (ref "U2") (pin "6") (pinfunction "GND_1_6") (pintype "passive"))
      (node (ref "U2") (pin "7") (pinfunction "GND_2_7") (pintype "passive"))
      (node (ref "U3") (pin "1") (pinfunction "ADJ/GND_1") (pintype "passive"))
      (node (ref "U4") (pin "A1") (pinfunction "GND_1_A1") (pintype "passive"))
      (node (ref "U4") (pin "A3") (pinfunction "GND_2_A3") (pintype "passive"))
      (node (ref "U4") (pin "A5") (pinfunction "GND_3_A5") (pintype "passive"))
      (node (ref "U4") (pin "A7") (pinfunction "GND_4_A7") (pintype "passive"))
      (node (ref "U4") (pin "A8") (pinfunction "GND_5_A8") (pintype "passive"))
      (node (ref "U4") (pin "A9") (pinfunction "GND_6_A9") (pintype "passive"))
      (node (ref "U4") (pin "B9") (pinfunction "GND_7_B9") (pintype "passive"))
      (node (ref "U4") (pin "C1") (pinfunction "SQI_D1_C1") (pintype "passive"))
      (node (ref "U4") (pin "C7") (pinfunction "GND_8_C7") (pintype "passive"))
      (node (ref "U4") (pin "C9") (pinfunction "GND_9_C9") (pintype "passive"))
      (node (ref "U4") (pin "D3") (pinfunction "SQI_CS_N_D3") (pintype "passive"))
      (node (ref "U4") (pin "D6") (pinfunction "GND_10_D6") (pintype "passive"))
      (node (ref "U4") (pin "D9") (pinfunction "GND_11_D9") (pintype "passive"))
      (node (ref "U4") (pin "E1") (pinfunction "SQI_CLK_E1") (pintype "passive"))
      (node (ref "U4") (pin "E3") (pinfunction "SQI_D2_E3") (pintype "passive"))
      (node (ref "U4") (pin "E7") (pinfunction "GND_12_E7") (pintype "passive"))
      (node (ref "U4") (pin "F7") (pinfunction "GND_13_F7") (pintype "passive"))
      (node (ref "U4") (pin "G3") (pinfunction "GND_14_G3") (pintype "passive"))
      (node (ref "U4") (pin "G6") (pinfunction "GND_15_G6") (pintype "passive"))
      (node (ref "U4") (pin "G7") (pinfunction "GND_16_G7") (pintype "passive"))
      (node (ref "U4") (pin "J3") (pinfunction "GND_17_J3") (pintype "passive"))
      (node (ref "U4") (pin "J9") (pinfunction "GND_18_J9") (pintype "passive"))
      (node (ref "U5") (pin "3") (pinfunction "GND_3") (pintype "power_in"))
      (node (ref "U5") (pin "4") (pinfunction "CSB_1_4") (pintype "input"))
      (node (ref "U6") (pin "10") (pinfunction "GND_10") (pintype "passive"))
      (node (ref "U7") (pin "2") (pinfunction "GND_1_2") (pintype "passive"))
      (node (ref "U7") (pin "25") (pinfunction "GND_2_25") (pintype "passive"))
    )
    (net (code "33") (name "Net-(C8-Pad2)") (class "Default")
      (node (ref "C8") (pin "2") (pinfunction "2_2") (pintype "passive"))
      (node (ref "L2") (pin "2") (pinfunction "2_2") (pintype "passive"))
      (node (ref "R8") (pin "2") (pinfunction "2_2") (pintype "passive"))
    )
    (net (code "34") (name "Net-(LED1-K)") (class "Default")
      (node (ref "LED1") (pin "1") (pinfunction "K_1") (pintype "passive"))
      (node (ref "R13") (pin "1") (pinfunction "1_1") (pintype "passive"))
    )
    (net (code "35") (name "Net-(LED2-K)") (class "Default")
      (node (ref "LED2") (pin "1") (pinfunction "K_1") (pintype "passive"))
      (node (ref "R4") (pin "1") (pinfunction "1_1") (pintype "passive"))
    )
    (net (code "36") (name "Net-(Q1-B)") (class "Default")
      (node (ref "Q1") (pin "1") (pinfunction "B_1") (pintype "passive"))
      (node (ref "R9") (pin "2") (pinfunction "2_2") (pintype "passive"))
    )
    (net (code "37") (name "Net-(Q2-B)") (class "Default")
      (node (ref "Q2") (pin "1") (pinfunction "B_1") (pintype "passive"))
      (node (ref "R10") (pin "2") (pinfunction "2_2") (pintype "passive"))
    )
    (net (code "38") (name "Net-(U2-CS)") (class "Default")
      (node (ref "R3") (pin "1") (pinfunction "1_1") (pintype "passive"))
      (node (ref "U2") (pin "12") (pinfunction "CS_12") (pintype "passive"))
    )
    (net (code "39") (name "Net-(U6-IO2)") (class "Default")
      (node (ref "R7") (pin "2") (pinfunction "2_2") (pintype "passive"))
      (node (ref "U6") (pin "9") (pinfunction "IO2_9") (pintype "passive"))
    )
    (net (code "40") (name "unconnected-(J4-Pad13)") (class "Default")
      (node (ref "J4") (pin "13") (pinfunction "13_13") (pintype "passive+no_connect"))
    )
    (net (code "41") (name "unconnected-(J4-Pad15)") (class "Default")
      (node (ref "J4") (pin "15") (pinfunction "15_15") (pintype "passive+no_connect"))
    )
    (net (code "42") (name "unconnected-(J4-Pad17)") (class "Default")
      (node (ref "J4") (pin "17") (pinfunction "17_17") (pintype "passive+no_connect"))
    )
    (net (code "43") (name "unconnected-(J4-Pad19)") (class "Default")
      (node (ref "J4") (pin "19") (pinfunction "19_19") (pintype "passive+no_connect"))
    )
    (net (code "44") (name "unconnected-(J4-Pad21)") (class "Default")
      (node (ref "J4") (pin "21") (pinfunction "21_21") (pintype "passive+no_connect"))
    )
    (net (code "45") (name "unconnected-(J4-Pad23)") (class "Default")
      (node (ref "J4") (pin "23") (pinfunction "23_23") (pintype "passive+no_connect"))
    )
    (net (code "46") (name "unconnected-(J5-ID-Pad4)") (class "Default")
      (node (ref "J5") (pin "4") (pinfunction "ID_4") (pintype "passive+no_connect"))
    )
    (net (code "47") (name "unconnected-(J5-Pad6)") (class "Default")
      (node (ref "J5") (pin "6") (pinfunction "6_6") (pintype "passive"))
    )
    (net (code "48") (name "unconnected-(J5-Pad7)") (class "Default")
      (node (ref "J5") (pin "7") (pinfunction "7_7") (pintype "passive+no_connect"))
    )
    (net (code "49") (name "unconnected-(J5-Pad8)") (class "Default")
      (node (ref "J5") (pin "8") (pinfunction "8_8") (pintype "passive+no_connect"))
    )
    (net (code "50") (name "unconnected-(J5-Pad9)") (class "Default")
      (node (ref "J5") (pin "9") (pinfunction "9_9") (pintype "passive+no_connect"))
    )
    (net (code "51") (name "unconnected-(J5-Pad10)") (class "Default")
      (node (ref "J5") (pin "10") (pinfunction "10_10") (pintype "passive+no_connect"))
    )
    (net (code "52") (name "unconnected-(J5-Pad11)") (class "Default")
      (node (ref "J5") (pin "11") (pinfunction "11_11") (pintype "passive+no_connect"))
    )
    (net (code "53") (name "unconnected-(J7-DAT1-Pad8)") (class "Default")
      (node (ref "J7") (pin "8") (pinfunction "DAT1_8") (pintype "passive+no_connect"))
    )
    (net (code "54") (name "unconnected-(J7-DATA2-Pad1)") (class "Default")
      (node (ref "J7") (pin "1") (pinfunction "DATA2_1") (pintype "passive+no_connect"))
    )
    (net (code "55") (name "unconnected-(S0-COM_1-Pad3)") (class "Default")
      (node (ref "S0") (pin "3") (pinfunction "COM_1_3") (pintype "passive"))
    )
    (net (code "56") (name "unconnected-(S0-NO_2-Pad2)") (class "Default")
      (node (ref "S0") (pin "2") (pinfunction "NO_2_2") (pintype "passive"))
    )
    (net (code "57") (name "unconnected-(S1-COM_1-Pad3)") (class "Default")
      (node (ref "S1") (pin "3") (pinfunction "COM_1_3") (pintype "passive"))
    )
    (net (code "58") (name "unconnected-(S1-NO_2-Pad2)") (class "Default")
      (node (ref "S1") (pin "2") (pinfunction "NO_2_2") (pintype "passive"))
    )
    (net (code "59") (name "unconnected-(U1-IO2-Pad24)") (class "Default")
      (node (ref "U1") (pin "24") (pinfunction "IO2_24") (pintype "passive+no_connect"))
    )
    (net (code "60") (name "unconnected-(U1-IO4-Pad26)") (class "Default")
      (node (ref "U1") (pin "26") (pinfunction "IO4_26") (pintype "passive+no_connect"))
    )
    (net (code "61") (name "unconnected-(U1-IO12-Pad14)") (class "Default")
      (node (ref "U1") (pin "14") (pinfunction "IO12_14") (pintype "passive+no_connect"))
    )
    (net (code "62") (name "unconnected-(U1-IO15-Pad23)") (class "Default")
      (node (ref "U1") (pin "23") (pinfunction "IO15_23") (pintype "passive+no_connect"))
    )
    (net (code "63") (name "unconnected-(U1-IO34-Pad6)") (class "Default")
      (node (ref "U1") (pin "6") (pinfunction "IO34_6") (pintype "passive+no_connect"))
    )
    (net (code "64") (name "unconnected-(U1-IO35-Pad7)") (class "Default")
      (node (ref "U1") (pin "7") (pinfunction "IO35_7") (pintype "passive+no_connect"))
    )
    (net (code "65") (name "unconnected-(U1-NC_1-Pad17)") (class "Default")
      (node (ref "U1") (pin "17") (pinfunction "NC_1_17") (pintype "passive+no_connect"))
    )
    (net (code "66") (name "unconnected-(U1-NC_2-Pad18)") (class "Default")
      (node (ref "U1") (pin "18") (pinfunction "NC_2_18") (pintype "passive+no_connect"))
    )
    (net (code "67") (name "unconnected-(U1-NC_3-Pad19)") (class "Default")
      (node (ref "U1") (pin "19") (pinfunction "NC_3_19") (pintype "passive+no_connect"))
    )
    (net (code "68") (name "unconnected-(U1-NC_4-Pad20)") (class "Default")
      (node (ref "U1") (pin "20") (pinfunction "NC_4_20") (pintype "passive+no_connect"))
    )
    (net (code "69") (name "unconnected-(U1-NC_5-Pad21)") (class "Default")
      (node (ref "U1") (pin "21") (pinfunction "NC_5_21") (pintype "passive+no_connect"))
    )
    (net (code "70") (name "unconnected-(U1-NC_6-Pad22)") (class "Default")
      (node (ref "U1") (pin "22") (pinfunction "NC_6_22") (pintype "passive+no_connect"))
    )
    (net (code "71") (name "unconnected-(U1-NC_7-Pad27)") (class "Default")
      (node (ref "U1") (pin "27") (pinfunction "NC_7_27") (pintype "passive+no_connect"))
    )
    (net (code "72") (name "unconnected-(U1-NC_8-Pad28)") (class "Default")
      (node (ref "U1") (pin "28") (pinfunction "NC_8_28") (pintype "passive+no_connect"))
    )
    (net (code "73") (name "unconnected-(U1-NC_9-Pad32)") (class "Default")
      (node (ref "U1") (pin "32") (pinfunction "NC_9_32") (pintype "passive+no_connect"))
    )
    (net (code "74") (name "unconnected-(U1-SENSOR_VN-Pad5)") (class "Default")
      (node (ref "U1") (pin "5") (pinfunction "SENSOR_VN_5") (pintype "passive+no_connect"))
    )
    (net (code "75") (name "unconnected-(U1-SENSOR_VP-Pad4)") (class "Default")
      (node (ref "U1") (pin "4") (pinfunction "SENSOR_VP_4") (pintype "passive+no_connect"))
    )
    (net (code "76") (name "unconnected-(U2-INT1-Pad4)") (class "Default")
      (node (ref "U2") (pin "4") (pinfunction "INT1_4") (pintype "passive+no_connect"))
    )
    (net (code "77") (name "unconnected-(U2-INT2-Pad9)") (class "Default")
      (node (ref "U2") (pin "9") (pinfunction "INT2_9") (pintype "passive+no_connect"))
    )
    (net (code "78") (name "unconnected-(U2-OCS_AUX-Pad10)") (class "Default")
      (node (ref "U2") (pin "10") (pinfunction "OCS_AUX_10") (pintype "passive+no_connect"))
    )
    (net (code "79") (name "unconnected-(U2-SDO_AUX-Pad11)") (class "Default")
      (node (ref "U2") (pin "11") (pinfunction "SDO_AUX_11") (pintype "passive+no_connect"))
    )
    (net (code "80") (name "unconnected-(U4-D_SEL-PadD4)") (class "Default")
      (node (ref "U4") (pin "D4") (pinfunction "D_SEL_D4") (pintype "passive+no_connect"))
    )
    (net (code "81") (name "unconnected-(U4-LNA_EN-PadC5)") (class "Default")
      (node (ref "U4") (pin "C5") (pinfunction "LNA_EN_C5") (pintype "passive+no_connect"))
    )
    (net (code "82") (name "unconnected-(U4-PIO13_{slash}_EXTINT-PadG4)") (class "Default")
      (node (ref "U4") (pin "G4") (pinfunction "PIO13_/_EXTINT_G4") (pintype "passive+no_connect"))
    )
    (net (code "83") (name "unconnected-(U4-PIO14-PadF6)") (class "Default")
      (node (ref "U4") (pin "F6") (pinfunction "PIO14_F6") (pintype "passive+no_connect"))
    )
    (net (code "84") (name "unconnected-(U4-PIO15-PadC6)") (class "Default")
      (node (ref "U4") (pin "C6") (pinfunction "PIO15_C6") (pintype "passive+no_connect"))
    )
    (net (code "85") (name "unconnected-(U4-RESERVED_1-PadA6)") (class "Default")
      (node (ref "U4") (pin "A6") (pinfunction "RESERVED_1_A6") (pintype "passive+no_connect"))
    )
    (net (code "86") (name "unconnected-(U4-RESERVED_2-PadE9)") (class "Default")
      (node (ref "U4") (pin "E9") (pinfunction "RESERVED_2_E9") (pintype "passive+no_connect"))
    )
    (net (code "87") (name "unconnected-(U4-RESERVED_3-PadF1)") (class "Default")
      (node (ref "U4") (pin "F1") (pinfunction "RESERVED_3_F1") (pintype "passive+no_connect"))
    )
    (net (code "88") (name "unconnected-(U4-RESERVED_4-PadF4)") (class "Default")
      (node (ref "U4") (pin "F4") (pinfunction "RESERVED_4_F4") (pintype "passive+no_connect"))
    )
    (net (code "89") (name "unconnected-(U4-RESERVED_5-PadF9)") (class "Default")
      (node (ref "U4") (pin "F9") (pinfunction "RESERVED_5_F9") (pintype "passive+no_connect"))
    )
    (net (code "90") (name "unconnected-(U4-RESERVED_6-PadG5)") (class "Default")
      (node (ref "U4") (pin "G5") (pinfunction "RESERVED_6_G5") (pintype "passive+no_connect"))
    )
    (net (code "91") (name "unconnected-(U4-RESERVED_7-PadG9)") (class "Default")
      (node (ref "U4") (pin "G9") (pinfunction "RESERVED_7_G9") (pintype "passive+no_connect"))
    )
    (net (code "92") (name "unconnected-(U4-RTC_I-PadJ7)") (class "Default")
      (node (ref "U4") (pin "J7") (pinfunction "RTC_I_J7") (pintype "passive+no_connect"))
    )
    (net (code "93") (name "unconnected-(U4-RTC_O-PadJ8)") (class "Default")
      (node (ref "U4") (pin "J8") (pinfunction "RTC_O_J8") (pintype "passive+no_connect"))
    )
    (net (code "94") (name "unconnected-(U4-SAFEBOOT_N-PadC4)") (class "Default")
      (node (ref "U4") (pin "C4") (pinfunction "SAFEBOOT_N_C4") (pintype "passive+no_connect"))
    )
    (net (code "95") (name "unconnected-(U4-SQI_D0-PadD1)") (class "Default")
      (node (ref "U4") (pin "D1") (pinfunction "SQI_D0_D1") (pintype "passive+no_connect"))
    )
    (net (code "96") (name "unconnected-(U4-SQI_D3-PadF3)") (class "Default")
      (node (ref "U4") (pin "F3") (pinfunction "SQI_D3_F3") (pintype "passive+no_connect"))
    )
    (net (code "97") (name "unconnected-(U4-TIMEPULSE-PadC3)") (class "Default")
      (node (ref "U4") (pin "C3") (pinfunction "TIMEPULSE_C3") (pintype "passive+no_connect"))
    )
    (net (code "98") (name "unconnected-(U5-CSB_2-Pad5)") (class "Default")
      (node (ref "U5") (pin "5") (pinfunction "CSB_2_5") (pintype "input+no_connect"))
    )
    (net (code "99") (name "unconnected-(U5-SDO-Pad6)") (class "Default")
      (node (ref "U5") (pin "6") (pinfunction "SDO_6") (pintype "output+no_connect"))
    )
    (net (code "100") (name "unconnected-(U6-NC_1-Pad4)") (class "Default")
      (node (ref "U6") (pin "4") (pinfunction "NC_1_4") (pintype "passive+no_connect"))
    )
    (net (code "101") (name "unconnected-(U6-NC_2-Pad5)") (class "Default")
      (node (ref "U6") (pin "5") (pinfunction "NC_2_5") (pintype "passive+no_connect"))
    )
    (net (code "102") (name "unconnected-(U6-NC_3-Pad6)") (class "Default")
      (node (ref "U6") (pin "6") (pinfunction "NC_3_6") (pintype "passive+no_connect"))
    )
    (net (code "103") (name "unconnected-(U6-NC_4-Pad11)") (class "Default")
      (node (ref "U6") (pin "11") (pinfunction "NC_4_11") (pintype "passive+no_connect"))
    )
    (net (code "104") (name "unconnected-(U6-NC_5-Pad12)") (class "Default")
      (node (ref "U6") (pin "12") (pinfunction "NC_5_12") (pintype "passive+no_connect"))
    )
    (net (code "105") (name "unconnected-(U6-NC_6-Pad13)") (class "Default")
      (node (ref "U6") (pin "13") (pinfunction "NC_6_13") (pintype "passive+no_connect"))
    )
    (net (code "106") (name "unconnected-(U6-NC_7-Pad14)") (class "Default")
      (node (ref "U6") (pin "14") (pinfunction "NC_7_14") (pintype "passive+no_connect"))
    )
    (net (code "107") (name "unconnected-(U7-CTS-Pad18)") (class "Default")
      (node (ref "U7") (pin "18") (pinfunction "CTS_18") (pintype "passive+no_connect"))
    )
    (net (code "108") (name "unconnected-(U7-DCD-Pad24)") (class "Default")
      (node (ref "U7") (pin "24") (pinfunction "DCD_24") (pintype "passive+no_connect"))
    )
    (net (code "109") (name "unconnected-(U7-DSR-Pad22)") (class "Default")
      (node (ref "U7") (pin "22") (pinfunction "DSR_22") (pintype "passive+no_connect"))
    )
    (net (code "110") (name "unconnected-(U7-GPIO.0_{slash}_TXT-Pad14)") (class "Default")
      (node (ref "U7") (pin "14") (pinfunction "GPIO.0_/_TXT_14") (pintype "passive+no_connect"))
    )
    (net (code "111") (name "unconnected-(U7-GPIO.1_{slash}_RXT-Pad13)") (class "Default")
      (node (ref "U7") (pin "13") (pinfunction "GPIO.1_/_RXT_13") (pintype "passive+no_connect"))
    )
    (net (code "112") (name "unconnected-(U7-GPIO.2_{slash}_RS485-Pad12)") (class "Default")
      (node (ref "U7") (pin "12") (pinfunction "GPIO.2_/_RS485_12") (pintype "passive+no_connect"))
    )
    (net (code "113") (name "unconnected-(U7-GPIO.3_{slash}_WAKEUP-Pad11)") (class "Default")
      (node (ref "U7") (pin "11") (pinfunction "GPIO.3_/_WAKEUP_11") (pintype "passive+no_connect"))
    )
    (net (code "114") (name "unconnected-(U7-NC_1-Pad10)") (class "Default")
      (node (ref "U7") (pin "10") (pinfunction "NC_1_10") (pintype "passive+no_connect"))
    )
    (net (code "115") (name "unconnected-(U7-NC_2-Pad16)") (class "Default")
      (node (ref "U7") (pin "16") (pinfunction "NC_2_16") (pintype "passive+no_connect"))
    )
    (net (code "116") (name "unconnected-(U7-RI_{slash}_CLK-Pad1)") (class "Default")
      (node (ref "U7") (pin "1") (pinfunction "RI_/_CLK_1") (pintype "passive+no_connect"))
    )
    (net (code "117") (name "unconnected-(U7-RSTB-Pad9)") (class "Default")
      (node (ref "U7") (pin "9") (pinfunction "RSTB_9") (pintype "passive+no_connect"))
    )
    (net (code "118") (name "unconnected-(U7-SUSPEND-Pad17)") (class "Default")
      (node (ref "U7") (pin "17") (pinfunction "SUSPEND_17") (pintype "passive+no_connect"))
    )
    (net (code "119") (name "unconnected-(U7-SUSPENDB-Pad15)") (class "Default")
      (node (ref "U7") (pin "15") (pinfunction "SUSPENDB_15") (pintype "passive+no_connect"))
    )
  )
)
